# mains.net
KiCad netlist of a schematic drawn in EAGLE
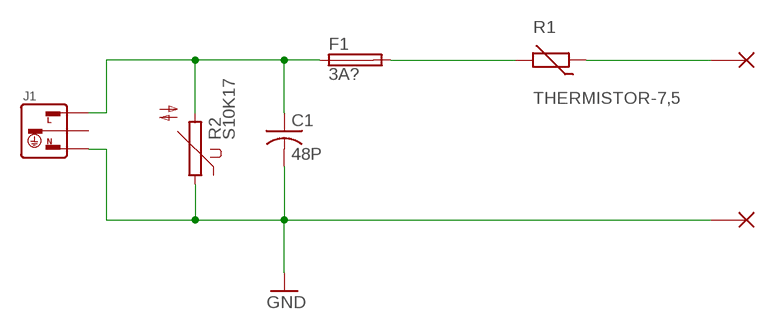
[diagram p0: schematic, sheet 1]

(export (version "E")
  (design (tool "Eeschema 10.0.6"))
  (components
    (comp (ref "C1")
      (value "48P")
      (footprint "eagle-import:C075")
      (libsource (lib "eagle-import") (part "C-075PTH"))
    )
    (comp (ref "F1")
      (value "3A?")
      (footprint "eagle-import:FUSE_HOLDER_5X20MM")
      (libsource (lib "eagle-import") (part "FUSEBLANK_5X20MM"))
    )
    (comp (ref "J1")
      (value "AC-JACK-3-ADAMTEC-IEC-A-4")
      (footprint "eagle-import:ADAMTEC-IEC-A-4")
      (libsource (lib "eagle-import") (part "AC-JACK-3-ADAMTEC-IEC-A-4"))
    )
    (comp (ref "R1")
      (value "THERMISTOR-7,5")
      (footprint "eagle-import:R-7,5")
      (libsource (lib "eagle-import") (part "THERMISTOR-7,5"))
    )
    (comp (ref "R2")
      (value "S10K17")
      (footprint "eagle-import:S10K17")
      (libsource (lib "eagle-import") (part "S10K17"))
    )
    (comp (ref "X3")
      (value "WIREPAD_14GA")
      (footprint "eagle-import:PAD_14GA")
      (libsource (lib "eagle-import") (part "WIREPAD_14GA"))
    )
    (comp (ref "X4")
      (value "WIREPAD_14GA")
      (footprint "eagle-import:PAD_14GA")
      (libsource (lib "eagle-import") (part "WIREPAD_14GA"))
    )
  )
  (nets
    (net (code "1") (name "GND") (class "Default")
      (node (ref "C1") (pin "2") (pinfunction "-_2") (pintype "passive"))
      (node (ref "J1") (pin "N") (pinfunction "N_N") (pintype "passive"))
      (node (ref "R2") (pin "1") (pinfunction "1_1") (pintype "passive"))
      (node (ref "X4") (pin "P$1") (pinfunction "P_P$1") (pintype "bidirectional"))
    )
    (net (code "2") (name "Net-(C1-+)") (class "Default")
      (node (ref "C1") (pin "1") (pinfunction "+_1") (pintype "passive"))
      (node (ref "F1") (pin "1") (pinfunction "1_1") (pintype "passive"))
      (node (ref "J1") (pin "L") (pinfunction "L_L") (pintype "passive"))
      (node (ref "R2") (pin "2") (pinfunction "2_2") (pintype "passive"))
    )
    (net (code "3") (name "Net-(F1-Pad2)") (class "Default")
      (node (ref "F1") (pin "2") (pinfunction "2_2") (pintype "passive"))
      (node (ref "R1") (pin "2") (pinfunction "2_2") (pintype "passive"))
    )
    (net (code "4") (name "Net-(X3-P)") (class "Default")
      (node (ref "R1") (pin "1") (pinfunction "1_1") (pintype "passive"))
      (node (ref "X3") (pin "P$1") (pinfunction "P_P$1") (pintype "bidirectional"))
    )
    (net (code "5") (name "unconnected-(J1-PadG)") (class "Default")
      (node (ref "J1") (pin "G") (pinfunction "G_G") (pintype "passive"))
    )
  )
)
